# adamonv2.net
KiCad netlist of a schematic drawn in EAGLE
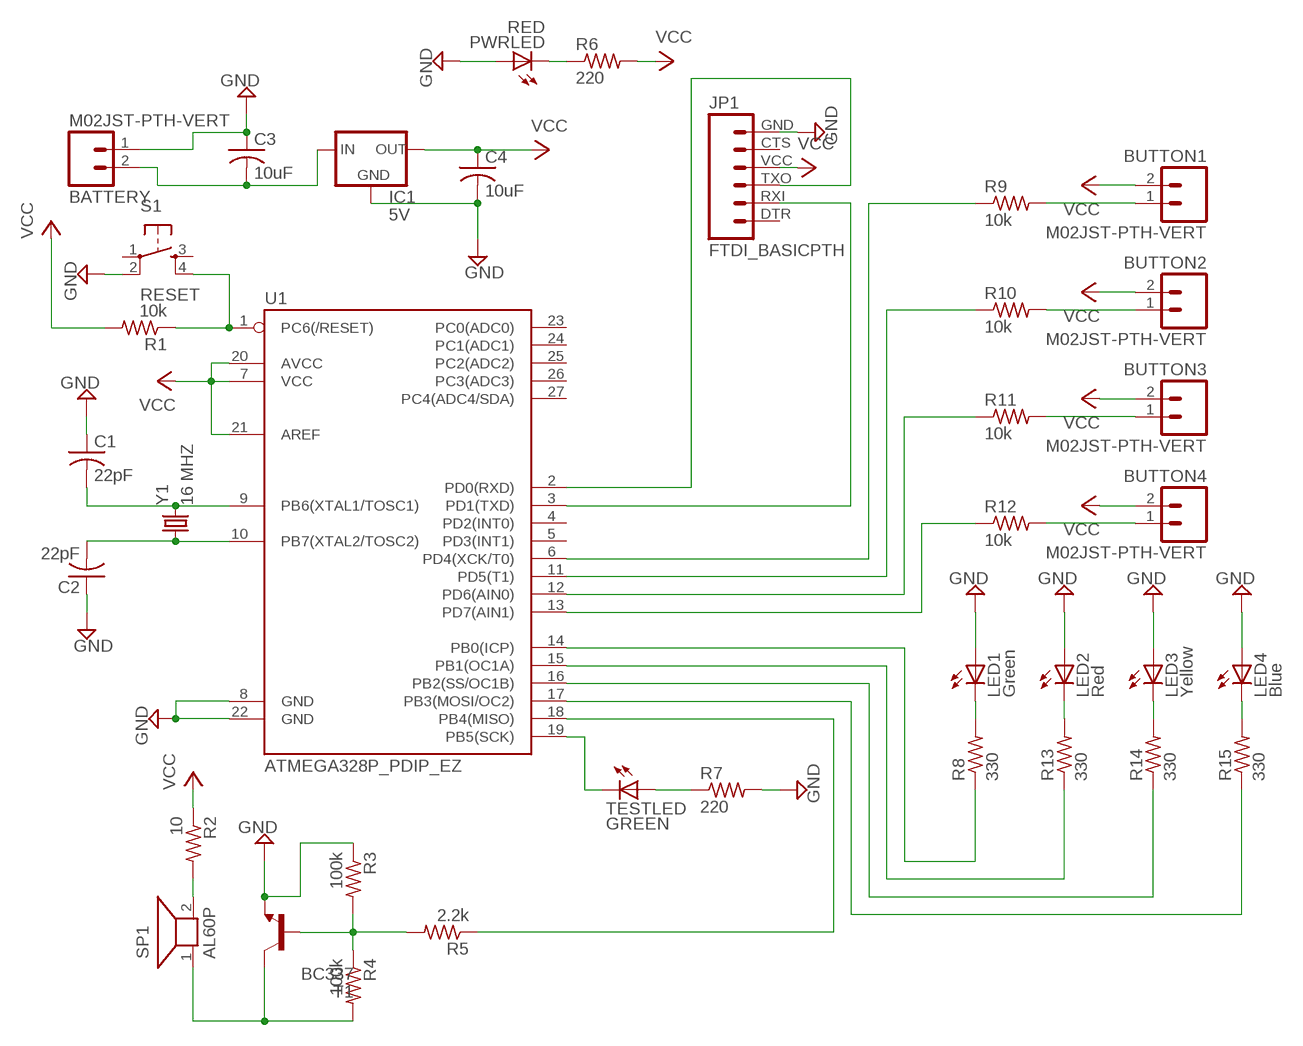
[diagram p0: schematic, sheet 1]

(export (version "E")
  (design (tool "Eeschema 10.0.6"))
  (components
    (comp (ref "BATTERY")
      (value "M02JST-PTH-VERT")
      (footprint "eagle-import:JST-2-PTH-VERT")
      (libsource (lib "eagle-import") (part "M02JST-PTH-VERT"))
    )
    (comp (ref "BUTTON1")
      (value "M02JST-PTH-VERT")
      (footprint "eagle-import:JST-2-PTH-VERT")
      (libsource (lib "eagle-import") (part "M02JST-PTH-VERT"))
    )
    (comp (ref "BUTTON2")
      (value "M02JST-PTH-VERT")
      (footprint "eagle-import:JST-2-PTH-VERT")
      (libsource (lib "eagle-import") (part "M02JST-PTH-VERT"))
    )
    (comp (ref "BUTTON3")
      (value "M02JST-PTH-VERT")
      (footprint "eagle-import:JST-2-PTH-VERT")
      (libsource (lib "eagle-import") (part "M02JST-PTH-VERT"))
    )
    (comp (ref "BUTTON4")
      (value "M02JST-PTH-VERT")
      (footprint "eagle-import:JST-2-PTH-VERT")
      (libsource (lib "eagle-import") (part "M02JST-PTH-VERT"))
    )
    (comp (ref "C1")
      (value "22pF")
      (footprint "eagle-import:C0805")
      (libsource (lib "eagle-import") (part "C-USC0805"))
    )
    (comp (ref "C2")
      (value "22pF")
      (footprint "eagle-import:C0805")
      (libsource (lib "eagle-import") (part "C-USC0805"))
    )
    (comp (ref "C3")
      (value "10uF")
      (footprint "eagle-import:C0805")
      (libsource (lib "eagle-import") (part "C-USC0805"))
    )
    (comp (ref "C4")
      (value "10uF")
      (footprint "eagle-import:C0805")
      (libsource (lib "eagle-import") (part "C-USC0805"))
    )
    (comp (ref "IC1")
      (value "5V")
      (footprint "eagle-import:TO220-IGO")
      (libsource (lib "eagle-import") (part "V_REG_78XXSINK"))
    )
    (comp (ref "JP1")
      (value "FTDI_BASICPTH")
      (footprint "eagle-import:FTDI_BASIC")
      (libsource (lib "eagle-import") (part "FTDI_BASICPTH"))
    )
    (comp (ref "LED1")
      (value "Green")
      (footprint "eagle-import:LED5MM")
      (libsource (lib "eagle-import") (part "LED5MM"))
    )
    (comp (ref "LED2")
      (value "Red")
      (footprint "eagle-import:LED5MM")
      (libsource (lib "eagle-import") (part "LED5MM"))
    )
    (comp (ref "LED3")
      (value "Yellow")
      (footprint "eagle-import:LED5MM")
      (libsource (lib "eagle-import") (part "LED5MM"))
    )
    (comp (ref "LED4")
      (value "Blue")
      (footprint "eagle-import:LED5MM")
      (libsource (lib "eagle-import") (part "LED5MM"))
    )
    (comp (ref "PWRLED")
      (value "RED")
      (footprint "eagle-import:CHIPLED_0805")
      (libsource (lib "eagle-import") (part "LEDCHIPLED_0805"))
    )
    (comp (ref "R1")
      (value "10k")
      (footprint "eagle-import:R0805")
      (libsource (lib "eagle-import") (part "resistor_R-US_R0805"))
    )
    (comp (ref "R2")
      (value "10")
      (footprint "eagle-import:R0805")
      (libsource (lib "eagle-import") (part "R-US_R0805"))
    )
    (comp (ref "R3")
      (value "100k")
      (footprint "eagle-import:R0805")
      (libsource (lib "eagle-import") (part "R-US_R0805"))
    )
    (comp (ref "R4")
      (value "100k")
      (footprint "eagle-import:R0805")
      (libsource (lib "eagle-import") (part "R-US_R0805"))
    )
    (comp (ref "R5")
      (value "2.2k")
      (footprint "eagle-import:R0805")
      (libsource (lib "eagle-import") (part "R-US_R0805"))
    )
    (comp (ref "R6")
      (value "220")
      (footprint "eagle-import:R0805")
      (libsource (lib "eagle-import") (part "resistor_R-US_R0805"))
    )
    (comp (ref "R7")
      (value "220")
      (footprint "eagle-import:R0805")
      (libsource (lib "eagle-import") (part "resistor_R-US_R0805"))
    )
    (comp (ref "R8")
      (value "330")
      (footprint "eagle-import:R0805")
      (libsource (lib "eagle-import") (part "R-US_R0805"))
    )
    (comp (ref "R9")
      (value "10k")
      (footprint "eagle-import:R0805")
      (libsource (lib "eagle-import") (part "R-US_R0805"))
    )
    (comp (ref "R10")
      (value "10k")
      (footprint "eagle-import:R0805")
      (libsource (lib "eagle-import") (part "R-US_R0805"))
    )
    (comp (ref "R11")
      (value "10k")
      (footprint "eagle-import:R0805")
      (libsource (lib "eagle-import") (part "R-US_R0805"))
    )
    (comp (ref "R12")
      (value "10k")
      (footprint "eagle-import:R0805")
      (libsource (lib "eagle-import") (part "R-US_R0805"))
    )
    (comp (ref "R13")
      (value "330")
      (footprint "eagle-import:R0805")
      (libsource (lib "eagle-import") (part "R-US_R0805"))
    )
    (comp (ref "R14")
      (value "330")
      (footprint "eagle-import:R0805")
      (libsource (lib "eagle-import") (part "R-US_R0805"))
    )
    (comp (ref "R15")
      (value "330")
      (footprint "eagle-import:R0805")
      (libsource (lib "eagle-import") (part "R-US_R0805"))
    )
    (comp (ref "S1")
      (value "RESET")
      (footprint "eagle-import:TACTILE_SWITCH_SMD")
      (libsource (lib "eagle-import") (part "TAC_SWITCHSMD"))
    )
    (comp (ref "SP1")
      (value "AL60P")
      (footprint "eagle-import:AL60P")
      (libsource (lib "eagle-import") (part "AL60P"))
    )
    (comp (ref "T1")
      (value "BC337")
      (footprint "eagle-import:TO92")
      (libsource (lib "eagle-import") (part "BC337"))
    )
    (comp (ref "TESTLED")
      (value "GREEN")
      (footprint "eagle-import:CHIPLED_0805")
      (libsource (lib "eagle-import") (part "LEDCHIPLED_0805"))
    )
    (comp (ref "U1")
      (value "ATMEGA328P_PDIP_EZ")
      (footprint "eagle-import:DIL28-EZ")
      (libsource (lib "eagle-import") (part "ATMEGA328P_PDIP_EZ"))
    )
    (comp (ref "Y1")
      (value "16 MHZ")
      (footprint "eagle-import:HC49US")
      (libsource (lib "eagle-import") (part "CRYSTALHC49US"))
    )
  )
  (nets
    (net (code "1") (name "GND") (class "Default")
      (node (ref "BATTERY") (pin "1") (pinfunction "1_1") (pintype "passive"))
      (node (ref "C1") (pin "1") (pinfunction "1_1") (pintype "passive"))
      (node (ref "C2") (pin "1") (pinfunction "1_1") (pintype "passive"))
      (node (ref "C3") (pin "1") (pinfunction "1_1") (pintype "passive"))
      (node (ref "C4") (pin "2") (pinfunction "2_2") (pintype "passive"))
      (node (ref "IC1") (pin "GND") (pinfunction "GND_GND") (pintype "input"))
      (node (ref "JP1") (pin "GND") (pinfunction "6_GND") (pintype "passive"))
      (node (ref "LED1") (pin "A") (pinfunction "A_A") (pintype "passive"))
      (node (ref "LED2") (pin "A") (pinfunction "A_A") (pintype "passive"))
      (node (ref "LED3") (pin "A") (pinfunction "A_A") (pintype "passive"))
      (node (ref "LED4") (pin "A") (pinfunction "A_A") (pintype "passive"))
      (node (ref "PWRLED") (pin "A") (pinfunction "A_A") (pintype "passive"))
      (node (ref "R3") (pin "1") (pinfunction "1_1") (pintype "passive"))
      (node (ref "R7") (pin "2") (pinfunction "2_2") (pintype "passive"))
      (node (ref "S1") (pin "2") (pinfunction "2_2") (pintype "passive"))
      (node (ref "T1") (pin "1") (pinfunction "E_1") (pintype "passive"))
      (node (ref "U1") (pin "22") (pinfunction "GND_22") (pintype "bidirectional"))
      (node (ref "U1") (pin "8") (pinfunction "GND_8") (pintype "bidirectional"))
    )
    (net (code "2") (name "Net-(BATTERY-Pad2)") (class "Default")
      (node (ref "BATTERY") (pin "2") (pinfunction "2_2") (pintype "passive"))
      (node (ref "C3") (pin "2") (pinfunction "2_2") (pintype "passive"))
      (node (ref "IC1") (pin "IN") (pinfunction "IN_IN") (pintype "input"))
    )
    (net (code "3") (name "Net-(BUTTON1-Pad1)") (class "Default")
      (node (ref "BUTTON1") (pin "1") (pinfunction "1_1") (pintype "passive"))
      (node (ref "R9") (pin "2") (pinfunction "2_2") (pintype "passive"))
    )
    (net (code "4") (name "Net-(BUTTON2-Pad1)") (class "Default")
      (node (ref "BUTTON2") (pin "1") (pinfunction "1_1") (pintype "passive"))
      (node (ref "R10") (pin "2") (pinfunction "2_2") (pintype "passive"))
    )
    (net (code "5") (name "Net-(BUTTON3-Pad1)") (class "Default")
      (node (ref "BUTTON3") (pin "1") (pinfunction "1_1") (pintype "passive"))
      (node (ref "R11") (pin "2") (pinfunction "2_2") (pintype "passive"))
    )
    (net (code "6") (name "Net-(BUTTON4-Pad1)") (class "Default")
      (node (ref "BUTTON4") (pin "1") (pinfunction "1_1") (pintype "passive"))
      (node (ref "R12") (pin "2") (pinfunction "2_2") (pintype "passive"))
    )
    (net (code "7") (name "Net-(JP1-2)") (class "Default")
      (node (ref "JP1") (pin "RXI") (pinfunction "2_RXI") (pintype "passive"))
      (node (ref "U1") (pin "3") (pinfunction "PD1(TXD)_3") (pintype "bidirectional"))
    )
    (net (code "8") (name "Net-(JP1-3)") (class "Default")
      (node (ref "JP1") (pin "TXO") (pinfunction "3_TXO") (pintype "passive"))
      (node (ref "U1") (pin "2") (pinfunction "PD0(RXD)_2") (pintype "bidirectional"))
    )
    (net (code "9") (name "Net-(LED1-C)") (class "Default")
      (node (ref "LED1") (pin "K") (pinfunction "C_K") (pintype "passive"))
      (node (ref "R8") (pin "2") (pinfunction "2_2") (pintype "passive"))
    )
    (net (code "10") (name "Net-(LED2-C)") (class "Default")
      (node (ref "LED2") (pin "K") (pinfunction "C_K") (pintype "passive"))
      (node (ref "R13") (pin "2") (pinfunction "2_2") (pintype "passive"))
    )
    (net (code "11") (name "Net-(LED3-C)") (class "Default")
      (node (ref "LED3") (pin "K") (pinfunction "C_K") (pintype "passive"))
      (node (ref "R14") (pin "2") (pinfunction "2_2") (pintype "passive"))
    )
    (net (code "12") (name "Net-(LED4-C)") (class "Default")
      (node (ref "LED4") (pin "K") (pinfunction "C_K") (pintype "passive"))
      (node (ref "R15") (pin "2") (pinfunction "2_2") (pintype "passive"))
    )
    (net (code "13") (name "Net-(PWRLED-PadC)") (class "Default")
      (node (ref "PWRLED") (pin "C") (pinfunction "C_C") (pintype "passive"))
      (node (ref "R6") (pin "1") (pinfunction "1_1") (pintype "passive"))
    )
    (net (code "14") (name "Net-(R2-Pad2)") (class "Default")
      (node (ref "R2") (pin "2") (pinfunction "2_2") (pintype "passive"))
      (node (ref "SP1") (pin "2") (pinfunction "2_2") (pintype "passive"))
    )
    (net (code "15") (name "Net-(R7-Pad1)") (class "Default")
      (node (ref "R7") (pin "1") (pinfunction "1_1") (pintype "passive"))
      (node (ref "TESTLED") (pin "A") (pinfunction "A_A") (pintype "passive"))
    )
    (net (code "16") (name "Net-(T1-B)") (class "Default")
      (node (ref "R3") (pin "2") (pinfunction "2_2") (pintype "passive"))
      (node (ref "R4") (pin "1") (pinfunction "1_1") (pintype "passive"))
      (node (ref "R5") (pin "2") (pinfunction "2_2") (pintype "passive"))
      (node (ref "T1") (pin "2") (pinfunction "B_2") (pintype "passive"))
    )
    (net (code "17") (name "Net-(T1-C)") (class "Default")
      (node (ref "R4") (pin "2") (pinfunction "2_2") (pintype "passive"))
      (node (ref "SP1") (pin "1") (pinfunction "1_1") (pintype "passive"))
      (node (ref "T1") (pin "3") (pinfunction "C_3") (pintype "passive"))
    )
    (net (code "18") (name "Net-(U1-PB0(ICP))") (class "Default")
      (node (ref "R8") (pin "1") (pinfunction "1_1") (pintype "passive"))
      (node (ref "U1") (pin "14") (pinfunction "PB0(ICP)_14") (pintype "bidirectional"))
    )
    (net (code "19") (name "Net-(U1-PB1(OC1A))") (class "Default")
      (node (ref "R13") (pin "1") (pinfunction "1_1") (pintype "passive"))
      (node (ref "U1") (pin "15") (pinfunction "PB1(OC1A)_15") (pintype "bidirectional"))
    )
    (net (code "20") (name "Net-(U1-PB2(SS{slash}OC1B))") (class "Default")
      (node (ref "R14") (pin "1") (pinfunction "1_1") (pintype "passive"))
      (node (ref "U1") (pin "16") (pinfunction "PB2(SS/OC1B)_16") (pintype "bidirectional"))
    )
    (net (code "21") (name "Net-(U1-PB3(MOSI{slash}OC2))") (class "Default")
      (node (ref "R15") (pin "1") (pinfunction "1_1") (pintype "passive"))
      (node (ref "U1") (pin "17") (pinfunction "PB3(MOSI/OC2)_17") (pintype "bidirectional"))
    )
    (net (code "22") (name "Net-(U1-PB4(MISO))") (class "Default")
      (node (ref "R5") (pin "1") (pinfunction "1_1") (pintype "passive"))
      (node (ref "U1") (pin "18") (pinfunction "PB4(MISO)_18") (pintype "bidirectional"))
    )
    (net (code "23") (name "Net-(U1-PB5(SCK))") (class "Default")
      (node (ref "TESTLED") (pin "C") (pinfunction "C_C") (pintype "passive"))
      (node (ref "U1") (pin "19") (pinfunction "PB5(SCK)_19") (pintype "bidirectional"))
    )
    (net (code "24") (name "Net-(U1-PB6(XTAL1{slash}TOSC1))") (class "Default")
      (node (ref "C1") (pin "2") (pinfunction "2_2") (pintype "passive"))
      (node (ref "U1") (pin "9") (pinfunction "PB6(XTAL1/TOSC1)_9") (pintype "bidirectional"))
      (node (ref "Y1") (pin "2") (pinfunction "2_2") (pintype "passive"))
    )
    (net (code "25") (name "Net-(U1-PB7(XTAL2{slash}TOSC2))") (class "Default")
      (node (ref "C2") (pin "2") (pinfunction "2_2") (pintype "passive"))
      (node (ref "U1") (pin "10") (pinfunction "PB7(XTAL2/TOSC2)_10") (pintype "bidirectional"))
      (node (ref "Y1") (pin "1") (pinfunction "1_1") (pintype "passive"))
    )
    (net (code "26") (name "Net-(U1-PC6({slash}RESET))") (class "Default")
      (node (ref "R1") (pin "1") (pinfunction "1_1") (pintype "passive"))
      (node (ref "S1") (pin "4") (pinfunction "4_4") (pintype "passive"))
      (node (ref "U1") (pin "1") (pinfunction "PC6(/RESET)_1") (pintype "bidirectional"))
    )
    (net (code "27") (name "Net-(U1-PD4(XCK{slash}T0))") (class "Default")
      (node (ref "R9") (pin "1") (pinfunction "1_1") (pintype "passive"))
      (node (ref "U1") (pin "6") (pinfunction "PD4(XCK/T0)_6") (pintype "bidirectional"))
    )
    (net (code "28") (name "Net-(U1-PD5(T1))") (class "Default")
      (node (ref "R10") (pin "1") (pinfunction "1_1") (pintype "passive"))
      (node (ref "U1") (pin "11") (pinfunction "PD5(T1)_11") (pintype "bidirectional"))
    )
    (net (code "29") (name "Net-(U1-PD6(AIN0))") (class "Default")
      (node (ref "R11") (pin "1") (pinfunction "1_1") (pintype "passive"))
      (node (ref "U1") (pin "12") (pinfunction "PD6(AIN0)_12") (pintype "bidirectional"))
    )
    (net (code "30") (name "Net-(U1-PD7(AIN1))") (class "Default")
      (node (ref "R12") (pin "1") (pinfunction "1_1") (pintype "passive"))
      (node (ref "U1") (pin "13") (pinfunction "PD7(AIN1)_13") (pintype "bidirectional"))
    )
    (net (code "31") (name "VCC") (class "Default")
      (node (ref "BUTTON1") (pin "2") (pinfunction "2_2") (pintype "passive"))
      (node (ref "BUTTON2") (pin "2") (pinfunction "2_2") (pintype "passive"))
      (node (ref "BUTTON3") (pin "2") (pinfunction "2_2") (pintype "passive"))
      (node (ref "BUTTON4") (pin "2") (pinfunction "2_2") (pintype "passive"))
      (node (ref "C4") (pin "1") (pinfunction "1_1") (pintype "passive"))
      (node (ref "IC1") (pin "OUT") (pinfunction "OUT_OUT") (pintype "output"))
      (node (ref "JP1") (pin "VCC") (pinfunction "4_VCC") (pintype "passive"))
      (node (ref "R1") (pin "2") (pinfunction "2_2") (pintype "passive"))
      (node (ref "R2") (pin "1") (pinfunction "1_1") (pintype "passive"))
      (node (ref "R6") (pin "2") (pinfunction "2_2") (pintype "passive"))
      (node (ref "U1") (pin "20") (pinfunction "AVCC_20") (pintype "bidirectional"))
      (node (ref "U1") (pin "21") (pinfunction "AREF_21") (pintype "bidirectional"))
      (node (ref "U1") (pin "7") (pinfunction "VCC_7") (pintype "bidirectional"))
    )
    (net (code "32") (name "unconnected-(JP1-1-PadDTR)") (class "Default")
      (node (ref "JP1") (pin "DTR") (pinfunction "1_DTR") (pintype "passive"))
    )
    (net (code "33") (name "unconnected-(JP1-5-PadCTS)") (class "Default")
      (node (ref "JP1") (pin "CTS") (pinfunction "5_CTS") (pintype "passive"))
    )
    (net (code "34") (name "unconnected-(S1-Pad1)") (class "Default")
      (node (ref "S1") (pin "1") (pinfunction "1_1") (pintype "passive"))
    )
    (net (code "35") (name "unconnected-(S1-Pad3)") (class "Default")
      (node (ref "S1") (pin "3") (pinfunction "3_3") (pintype "passive"))
    )
    (net (code "36") (name "unconnected-(U1-PC0(ADC0)-Pad23)") (class "Default")
      (node (ref "U1") (pin "23") (pinfunction "PC0(ADC0)_23") (pintype "bidirectional"))
    )
    (net (code "37") (name "unconnected-(U1-PC1(ADC1)-Pad24)") (class "Default")
      (node (ref "U1") (pin "24") (pinfunction "PC1(ADC1)_24") (pintype "bidirectional"))
    )
    (net (code "38") (name "unconnected-(U1-PC2(ADC2)-Pad25)") (class "Default")
      (node (ref "U1") (pin "25") (pinfunction "PC2(ADC2)_25") (pintype "bidirectional"))
    )
    (net (code "39") (name "unconnected-(U1-PC3(ADC3)-Pad26)") (class "Default")
      (node (ref "U1") (pin "26") (pinfunction "PC3(ADC3)_26") (pintype "bidirectional"))
    )
    (net (code "40") (name "unconnected-(U1-PC4(ADC4{slash}SDA)-Pad27)") (class "Default")
      (node (ref "U1") (pin "27") (pinfunction "PC4(ADC4/SDA)_27") (pintype "bidirectional"))
    )
    (net (code "41") (name "unconnected-(U1-PD2(INT0)-Pad4)") (class "Default")
      (node (ref "U1") (pin "4") (pinfunction "PD2(INT0)_4") (pintype "bidirectional"))
    )
    (net (code "42") (name "unconnected-(U1-PD3(INT1)-Pad5)") (class "Default")
      (node (ref "U1") (pin "5") (pinfunction "PD3(INT1)_5") (pintype "bidirectional"))
    )
  )
)
